# GNSS_Splitter.net
KiCad netlist of a schematic drawn in EAGLE
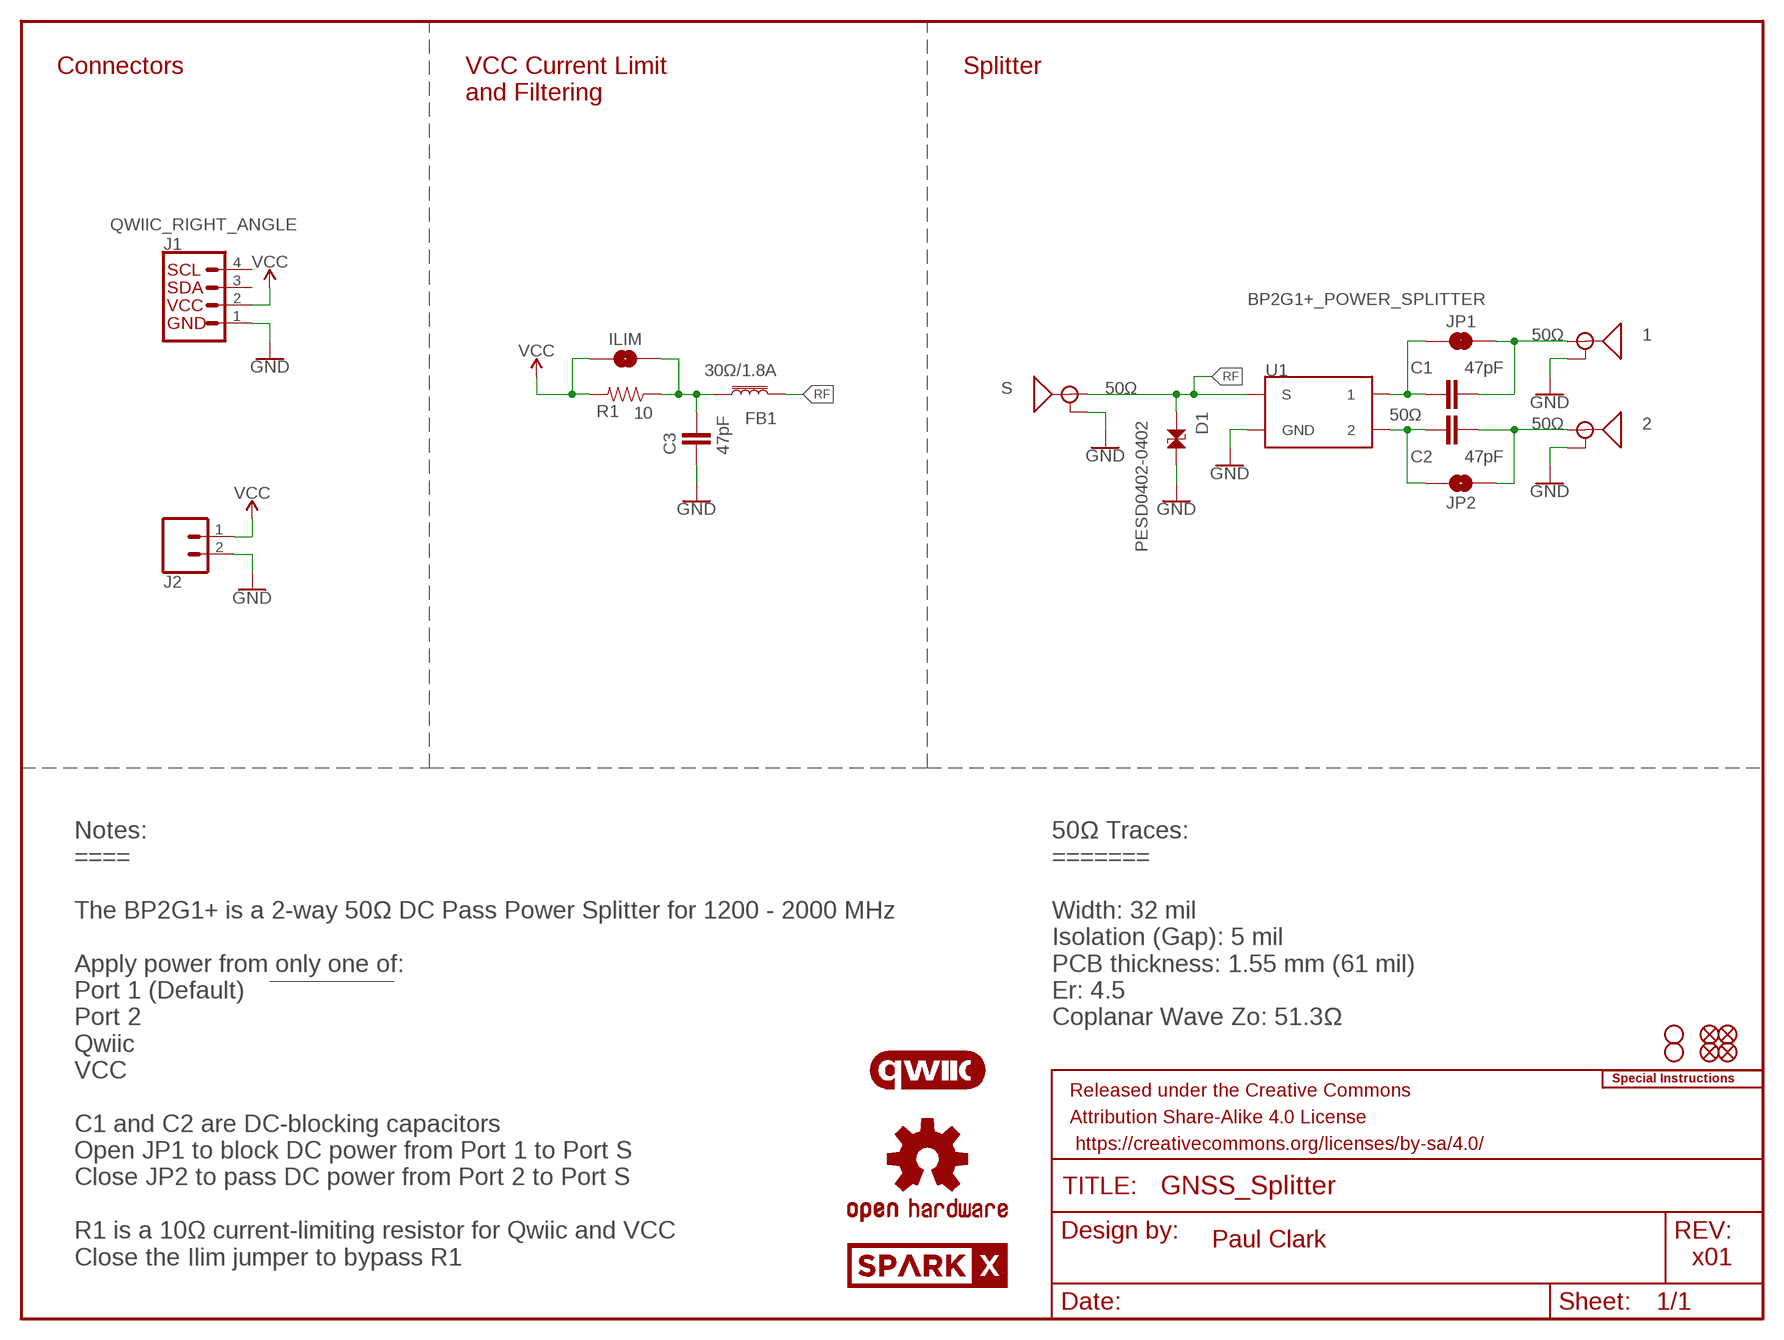
[diagram p0: schematic, sheet 1]

(export (version "E")
  (design (tool "Eeschema 10.0.6"))
  (components
    (comp (ref "1")
      (value "ANTENNA-SMA-GROUNDEDEDGE_SMA")
      (footprint "eagle-import:SMA-EDGE")
      (libsource (lib "eagle-import") (part "ANTENNA-SMA-GROUNDEDEDGE_SMA"))
    )
    (comp (ref "2")
      (value "ANTENNA-SMA-GROUNDEDEDGE_SMA")
      (footprint "eagle-import:SMA-EDGE")
      (libsource (lib "eagle-import") (part "ANTENNA-SMA-GROUNDEDEDGE_SMA"))
    )
    (comp (ref "C1")
      (value "47pF")
      (footprint "eagle-import:0603")
      (libsource (lib "eagle-import") (part "47PF-0603-50V-5%"))
    )
    (comp (ref "C2")
      (value "47pF")
      (footprint "eagle-import:0603")
      (libsource (lib "eagle-import") (part "47PF-0603-50V-5%"))
    )
    (comp (ref "C3")
      (value "47pF")
      (footprint "eagle-import:0603")
      (libsource (lib "eagle-import") (part "47PF-0603-50V-5%"))
    )
    (comp (ref "D1")
      (value "PESD0402-0402")
      (footprint "eagle-import:0402")
      (fields
        (field (name "DIGIKEY_PART") "PESD0402-140CT-ND")
        (field (name "MOUSE_PART") "650-PESD0402-140")
      )
      (libsource (lib "eagle-import") (part "PESD0402-0402"))
    )
    (comp (ref "FB1")
      (value "30Ω/1.8A")
      (footprint "eagle-import:0603")
      (libsource (lib "eagle-import") (part "FERRITE_BEAD-0603"))
    )
    (comp (ref "FD1")
      (value "FIDUCIAL1X2")
      (footprint "eagle-import:FIDUCIAL-1X2")
      (libsource (lib "eagle-import") (part "FIDUCIAL1X2"))
    )
    (comp (ref "FD2")
      (value "FIDUCIAL1X2")
      (footprint "eagle-import:FIDUCIAL-1X2")
      (libsource (lib "eagle-import") (part "FIDUCIAL1X2"))
    )
    (comp (ref "FD3")
      (value "FIDUCIAL1X2")
      (footprint "eagle-import:FIDUCIAL-1X2")
      (libsource (lib "eagle-import") (part "FIDUCIAL1X2"))
    )
    (comp (ref "FD4")
      (value "FIDUCIAL1X2")
      (footprint "eagle-import:FIDUCIAL-1X2")
      (libsource (lib "eagle-import") (part "FIDUCIAL1X2"))
    )
    (comp (ref "FRAME1")
      (value "FRAME-LETTER")
      (footprint "eagle-import:CREATIVE_COMMONS")
      (libsource (lib "eagle-import") (part "FRAME-LETTER"))
    )
    (comp (ref "H1")
      (value "STAND-OFF")
      (footprint "eagle-import:STAND-OFF")
      (libsource (lib "eagle-import") (part "STAND-OFF"))
    )
    (comp (ref "H2")
      (value "STAND-OFF")
      (footprint "eagle-import:STAND-OFF")
      (libsource (lib "eagle-import") (part "STAND-OFF"))
    )
    (comp (ref "ILIM")
      (value "JUMPER-SMT_2_NO_SILK")
      (footprint "eagle-import:SMT-JUMPER_2_NO_SILK")
      (libsource (lib "eagle-import") (part "JUMPER-SMT_2_NO_SILK"))
    )
    (comp (ref "J1")
      (value "QWIIC_RIGHT_ANGLE")
      (footprint "eagle-import:JST04_1MM_RA")
      (libsource (lib "eagle-import") (part "QWIIC_CONNECTORJS-1MM"))
    )
    (comp (ref "J2")
      (value "CONN_021X02_NO_SILK")
      (footprint "eagle-import:1X02_NO_SILK")
      (libsource (lib "eagle-import") (part "CONN_021X02_NO_SILK"))
    )
    (comp (ref "JP1")
      (value "JUMPER-SMT_2_NC_TRACE_SILK")
      (footprint "eagle-import:SMT-JUMPER_2_NC_TRACE_SILK")
      (libsource (lib "eagle-import") (part "JUMPER-SMT_2_NC_TRACE_SILK"))
    )
    (comp (ref "JP2")
      (value "JUMPER-SMT_2_NO_SILK")
      (footprint "eagle-import:SMT-JUMPER_2_NO_SILK")
      (libsource (lib "eagle-import") (part "JUMPER-SMT_2_NO_SILK"))
    )
    (comp (ref "LOGO1")
      (value "OSHW-LOGOS")
      (footprint "eagle-import:OSHW-LOGO-S")
      (libsource (lib "eagle-import") (part "OSHW-LOGOS"))
    )
    (comp (ref "LOGO2")
      (value "QWIIC_LOGO_6MM")
      (footprint "eagle-import:QWIIC_6MM")
      (libsource (lib "eagle-import") (part "QWIIC_LOGO_6MM"))
    )
    (comp (ref "LOGO3")
      (value "SPECIAL_INSTRUCTIONS-ORDERING")
      (footprint "eagle-import:ORDERING_INSTRUCTIONS")
      (libsource (lib "eagle-import") (part "SPECIAL_INSTRUCTIONS-ORDERING"))
    )
    (comp (ref "R1")
      (value "10")
      (footprint "eagle-import:0603")
      (libsource (lib "eagle-import") (part "10OHM-0603-1/10W-1%"))
    )
    (comp (ref "S")
      (value "ANTENNA-SMA-GROUNDEDEDGE_SMA")
      (footprint "eagle-import:SMA-EDGE")
      (libsource (lib "eagle-import") (part "ANTENNA-SMA-GROUNDEDEDGE_SMA"))
    )
    (comp (ref "U$1")
      (value "SPARKX-LOGO3")
      (footprint "eagle-import:SPARKX-SMALL")
      (libsource (lib "eagle-import") (part "SPARKX-LOGO3"))
    )
    (comp (ref "U$2")
      (value "SPARKX-LOGO3")
      (footprint "eagle-import:SPARKX-SMALL")
      (libsource (lib "eagle-import") (part "SPARKX-LOGO3"))
    )
    (comp (ref "U1")
      (value "BP2G1+_POWER_SPLITTER")
      (footprint "eagle-import:XX21")
      (libsource (lib "eagle-import") (part "BP2G1+_POWER_SPLITTER"))
    )
  )
  (nets
    (net (code "1") (name "GND") (class "Default")
      (node (ref "1") (pin "GND@0") (pinfunction "GND_GND@0") (pintype "bidirectional"))
      (node (ref "1") (pin "GND@1") (pinfunction "GND_GND@1") (pintype "bidirectional"))
      (node (ref "1") (pin "GND@2") (pinfunction "GND_GND@2") (pintype "bidirectional"))
      (node (ref "1") (pin "GND@3") (pinfunction "GND_GND@3") (pintype "bidirectional"))
      (node (ref "2") (pin "GND@0") (pinfunction "GND_GND@0") (pintype "bidirectional"))
      (node (ref "2") (pin "GND@1") (pinfunction "GND_GND@1") (pintype "bidirectional"))
      (node (ref "2") (pin "GND@2") (pinfunction "GND_GND@2") (pintype "bidirectional"))
      (node (ref "2") (pin "GND@3") (pinfunction "GND_GND@3") (pintype "bidirectional"))
      (node (ref "C3") (pin "1") (pinfunction "1_1") (pintype "passive"))
      (node (ref "D1") (pin "2") (pinfunction "2_2") (pintype "bidirectional"))
      (node (ref "J1") (pin "1") (pinfunction "1_1") (pintype "power_in"))
      (node (ref "J2") (pin "2") (pinfunction "2_2") (pintype "passive"))
      (node (ref "S") (pin "GND@0") (pinfunction "GND_GND@0") (pintype "bidirectional"))
      (node (ref "S") (pin "GND@1") (pinfunction "GND_GND@1") (pintype "bidirectional"))
      (node (ref "S") (pin "GND@2") (pinfunction "GND_GND@2") (pintype "bidirectional"))
      (node (ref "S") (pin "GND@3") (pinfunction "GND_GND@3") (pintype "bidirectional"))
      (node (ref "U1") (pin "1") (pinfunction "GND_1") (pintype "bidirectional"))
      (node (ref "U1") (pin "3") (pinfunction "GND_3") (pintype "bidirectional"))
      (node (ref "U1") (pin "4") (pinfunction "GND_4") (pintype "bidirectional"))
      (node (ref "U1") (pin "6") (pinfunction "GND_6") (pintype "bidirectional"))
      (node (ref "U1") (pin "7") (pinfunction "GND_7") (pintype "bidirectional"))
    )
    (net (code "2") (name "Net-(1-SIGNAL)") (class "Default")
      (node (ref "1") (pin "SIG") (pinfunction "SIGNAL_SIG") (pintype "bidirectional"))
      (node (ref "C1") (pin "2") (pinfunction "2_2") (pintype "passive"))
      (node (ref "JP1") (pin "2") (pinfunction "2_2") (pintype "passive"))
    )
    (net (code "3") (name "Net-(2-SIGNAL)") (class "Default")
      (node (ref "2") (pin "SIG") (pinfunction "SIGNAL_SIG") (pintype "bidirectional"))
      (node (ref "C2") (pin "1") (pinfunction "1_1") (pintype "passive"))
      (node (ref "JP2") (pin "1") (pinfunction "1_1") (pintype "passive"))
    )
    (net (code "4") (name "Net-(C3-Pad2)") (class "Default")
      (node (ref "C3") (pin "2") (pinfunction "2_2") (pintype "passive"))
      (node (ref "FB1") (pin "1") (pinfunction "1_1") (pintype "passive"))
      (node (ref "ILIM") (pin "2") (pinfunction "2_2") (pintype "passive"))
      (node (ref "R1") (pin "1") (pinfunction "1_1") (pintype "passive"))
    )
    (net (code "5") (name "Net-(U1-1)") (class "Default")
      (node (ref "C1") (pin "1") (pinfunction "1_1") (pintype "passive"))
      (node (ref "JP1") (pin "1") (pinfunction "1_1") (pintype "passive"))
      (node (ref "U1") (pin "8") (pinfunction "1_8") (pintype "bidirectional"))
    )
    (net (code "6") (name "Net-(U1-2)") (class "Default")
      (node (ref "C2") (pin "2") (pinfunction "2_2") (pintype "passive"))
      (node (ref "JP2") (pin "2") (pinfunction "2_2") (pintype "passive"))
      (node (ref "U1") (pin "5") (pinfunction "2_5") (pintype "bidirectional"))
    )
    (net (code "7") (name "RF") (class "Default")
      (node (ref "D1") (pin "1") (pinfunction "1_1") (pintype "bidirectional"))
      (node (ref "FB1") (pin "2") (pinfunction "2_2") (pintype "passive"))
      (node (ref "S") (pin "SIG") (pinfunction "SIGNAL_SIG") (pintype "bidirectional"))
      (node (ref "U1") (pin "2") (pinfunction "S_2") (pintype "bidirectional"))
    )
    (net (code "8") (name "VCC") (class "Default")
      (node (ref "ILIM") (pin "1") (pinfunction "1_1") (pintype "passive"))
      (node (ref "J1") (pin "2") (pinfunction "2_2") (pintype "power_in"))
      (node (ref "J2") (pin "1") (pinfunction "1_1") (pintype "passive"))
      (node (ref "R1") (pin "2") (pinfunction "2_2") (pintype "passive"))
    )
    (net (code "9") (name "unconnected-(J1-Pad3)") (class "Default")
      (node (ref "J1") (pin "3") (pinfunction "3_3") (pintype "passive"))
    )
    (net (code "10") (name "unconnected-(J1-Pad4)") (class "Default")
      (node (ref "J1") (pin "4") (pinfunction "4_4") (pintype "passive"))
    )
  )
)
